# napajeniMOB.net
KiCad netlist of a schematic drawn in EAGLE
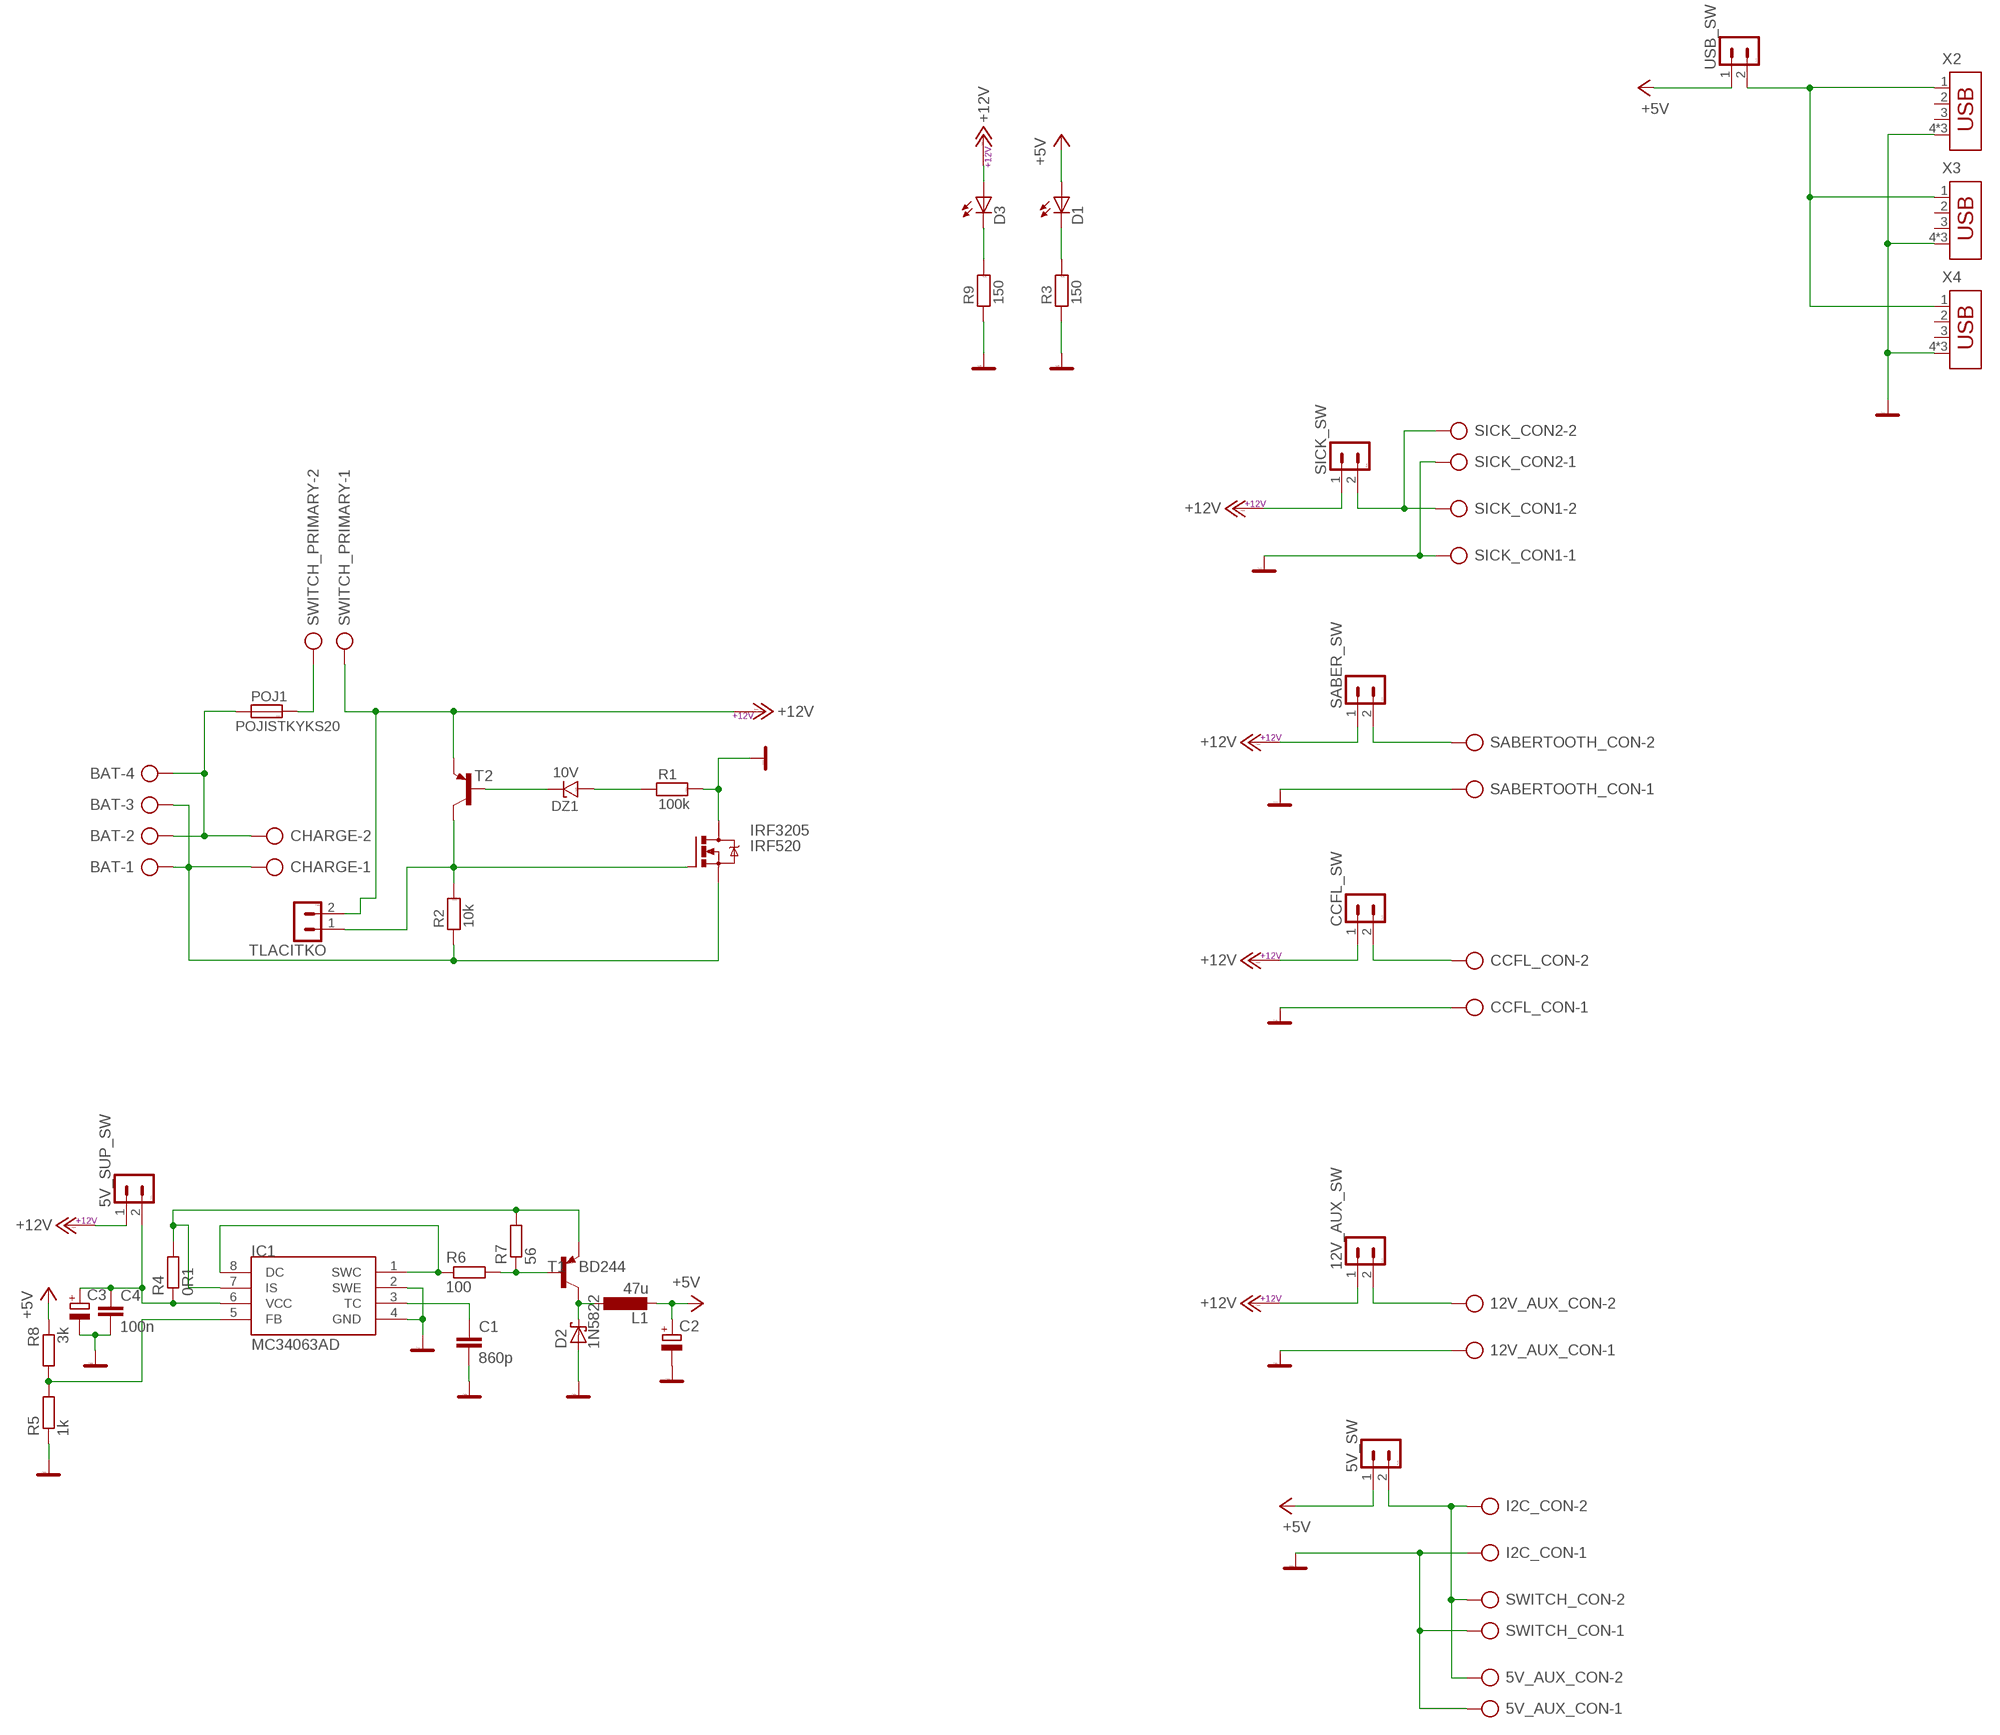
[diagram p0: schematic, sheet 1]

(export (version "E")
  (design (tool "Eeschema 10.0.6"))
  (components
    (comp (ref "5V_AUX_CON")
      (value "AK500/2")
      (footprint "eagle-import:AK500_2")
      (libsource (lib "eagle-import") (part "AK500/2"))
    )
    (comp (ref "5V_SUP_SW")
      (value "PSH02-02P")
      (footprint "eagle-import:PSH02-02P")
      (libsource (lib "eagle-import") (part "PSH02-02P"))
    )
    (comp (ref "5V_SW")
      (value "PSH02-02P")
      (footprint "eagle-import:PSH02-02P")
      (libsource (lib "eagle-import") (part "PSH02-02P"))
    )
    (comp (ref "12V_AUX_CON")
      (value "AK500/2")
      (footprint "eagle-import:AK500_2")
      (libsource (lib "eagle-import") (part "AK500/2"))
    )
    (comp (ref "12V_AUX_SW")
      (value "PSH02-02P")
      (footprint "eagle-import:PSH02-02P")
      (libsource (lib "eagle-import") (part "PSH02-02P"))
    )
    (comp (ref "BAT")
      (value "AK500/4")
      (footprint "eagle-import:AK500_4")
      (libsource (lib "eagle-import") (part "AK500/4"))
    )
    (comp (ref "C1")
      (value "860p")
      (footprint "eagle-import:C0805")
      (libsource (lib "eagle-import") (part "C-EUC0805"))
    )
    (comp (ref "C2")
      (value "CPOL-EUE5-8.5")
      (footprint "eagle-import:E5-8,5")
      (libsource (lib "eagle-import") (part "CPOL-EUE5-8.5"))
    )
    (comp (ref "C3")
      (value "CPOL-EUE5-8.5")
      (footprint "eagle-import:E5-8,5")
      (libsource (lib "eagle-import") (part "CPOL-EUE5-8.5"))
    )
    (comp (ref "C4")
      (value "100n")
      (footprint "eagle-import:C0805")
      (libsource (lib "eagle-import") (part "C-EUC0805"))
    )
    (comp (ref "CCFL_CON")
      (value "AK500/2")
      (footprint "eagle-import:AK500_2")
      (libsource (lib "eagle-import") (part "AK500/2"))
    )
    (comp (ref "CCFL_SW")
      (value "PSH02-02P")
      (footprint "eagle-import:PSH02-02P")
      (libsource (lib "eagle-import") (part "PSH02-02P"))
    )
    (comp (ref "CHARGE")
      (value "AK500/2")
      (footprint "eagle-import:AK500_2")
      (libsource (lib "eagle-import") (part "AK500/2"))
    )
    (comp (ref "D1")
      (value "LED3MM")
      (footprint "eagle-import:LED3MM")
      (libsource (lib "eagle-import") (part "LED3MM"))
    )
    (comp (ref "D2")
      (value "1N5822")
      (footprint "eagle-import:DO41-7.6")
      (libsource (lib "eagle-import") (part "1N5817-B"))
    )
    (comp (ref "D3")
      (value "LED3MM")
      (footprint "eagle-import:LED3MM")
      (libsource (lib "eagle-import") (part "LED3MM"))
    )
    (comp (ref "DZ1")
      (value "10V")
      (footprint "eagle-import:SOD-80")
      (libsource (lib "eagle-import") (part "D-ZENEROVA_0,5W_BZV55C_SMD"))
    )
    (comp (ref "I2C_CON")
      (value "AK500/2")
      (footprint "eagle-import:AK500_2")
      (libsource (lib "eagle-import") (part "AK500/2"))
    )
    (comp (ref "IC1")
      (value "MC34063AD")
      (footprint "eagle-import:SOIC8")
      (libsource (lib "eagle-import") (part "MC34063AD"))
    )
    (comp (ref "IRF3205")
      (value "IRF520")
      (footprint "eagle-import:TO220BV")
      (libsource (lib "eagle-import") (part "IRF520"))
    )
    (comp (ref "L1")
      (value "47u")
      (footprint "eagle-import:TJ3-U1")
      (libsource (lib "eagle-import") (part "L-EUTJ3-U1"))
    )
    (comp (ref "POJ1")
      (value "POJISTKYKS20")
      (footprint "eagle-import:POJ_KS20")
      (libsource (lib "eagle-import") (part "POJISTKYKS20"))
    )
    (comp (ref "R1")
      (value "100k")
      (footprint "eagle-import:0805")
      (libsource (lib "eagle-import") (part "R_SMD_0805"))
    )
    (comp (ref "R2")
      (value "10k")
      (footprint "eagle-import:0805")
      (libsource (lib "eagle-import") (part "R_SMD_0805"))
    )
    (comp (ref "R3")
      (value "150")
      (footprint "eagle-import:0805")
      (libsource (lib "eagle-import") (part "R_SMD_0805"))
    )
    (comp (ref "R4")
      (value "0R1")
      (footprint "eagle-import:M0805")
      (libsource (lib "eagle-import") (part "R-EU_M0805"))
    )
    (comp (ref "R5")
      (value "1k")
      (footprint "eagle-import:M0805")
      (libsource (lib "eagle-import") (part "R-EU_M0805"))
    )
    (comp (ref "R6")
      (value "100")
      (footprint "eagle-import:M0805")
      (libsource (lib "eagle-import") (part "R-EU_M0805"))
    )
    (comp (ref "R7")
      (value "56")
      (footprint "eagle-import:M0805")
      (libsource (lib "eagle-import") (part "R-EU_M0805"))
    )
    (comp (ref "R8")
      (value "3k")
      (footprint "eagle-import:M0805")
      (libsource (lib "eagle-import") (part "R-EU_M0805"))
    )
    (comp (ref "R9")
      (value "150")
      (footprint "eagle-import:0805")
      (libsource (lib "eagle-import") (part "R_SMD_0805"))
    )
    (comp (ref "SABERTOOTH_CON")
      (value "AK500/2")
      (footprint "eagle-import:AK500_2")
      (libsource (lib "eagle-import") (part "AK500/2"))
    )
    (comp (ref "SABER_SW")
      (value "PSH02-02P")
      (footprint "eagle-import:PSH02-02P")
      (libsource (lib "eagle-import") (part "PSH02-02P"))
    )
    (comp (ref "SICK_CON1")
      (value "AK500/2")
      (footprint "eagle-import:AK500_2")
      (libsource (lib "eagle-import") (part "AK500/2"))
    )
    (comp (ref "SICK_CON2")
      (value "AK500/2")
      (footprint "eagle-import:AK500_2")
      (libsource (lib "eagle-import") (part "AK500/2"))
    )
    (comp (ref "SICK_SW")
      (value "PSH02-02P")
      (footprint "eagle-import:PSH02-02P")
      (libsource (lib "eagle-import") (part "PSH02-02P"))
    )
    (comp (ref "SWITCH_CON")
      (value "AK500/2")
      (footprint "eagle-import:AK500_2")
      (libsource (lib "eagle-import") (part "AK500/2"))
    )
    (comp (ref "SWITCH_PRIMARY")
      (value "AK500/2")
      (footprint "eagle-import:AK500_2")
      (libsource (lib "eagle-import") (part "AK500/2"))
    )
    (comp (ref "T1")
      (value "BD244")
      (footprint "eagle-import:TO220")
      (libsource (lib "eagle-import") (part "BD244"))
    )
    (comp (ref "T2")
      (value "BC807-16-PNP-SOT23-BEC")
      (footprint "eagle-import:SOT23-BEC")
      (libsource (lib "eagle-import") (part "-PNP-SOT23-BECBC807-16"))
    )
    (comp (ref "TLACITKO")
      (value "PSH02-02P")
      (footprint "eagle-import:PSH02-02P")
      (libsource (lib "eagle-import") (part "PSH02-02P"))
    )
    (comp (ref "USB_SW")
      (value "PSH02-02P")
      (footprint "eagle-import:PSH02-02P")
      (libsource (lib "eagle-import") (part "PSH02-02P"))
    )
    (comp (ref "X2")
      (value "USB-787616GROUNDED")
      (footprint "eagle-import:USBGROUNDED")
      (libsource (lib "eagle-import") (part "USB-787616GROUNDED"))
    )
    (comp (ref "X3")
      (value "USB-787616GROUNDED")
      (footprint "eagle-import:USBGROUNDED")
      (libsource (lib "eagle-import") (part "USB-787616GROUNDED"))
    )
    (comp (ref "X4")
      (value "USB-787616GROUNDED")
      (footprint "eagle-import:USBGROUNDED")
      (libsource (lib "eagle-import") (part "USB-787616GROUNDED"))
    )
  )
  (nets
    (net (code "1") (name "+5V") (class "Default")
      (node (ref "5V_SW") (pin "1") (pinfunction "1_1") (pintype "passive"))
      (node (ref "C2") (pin "+") (pinfunction "+_+") (pintype "passive"))
      (node (ref "D1") (pin "A") (pinfunction "A_A") (pintype "passive"))
      (node (ref "L1") (pin "2") (pinfunction "2_2") (pintype "passive"))
      (node (ref "R8") (pin "1") (pinfunction "1_1") (pintype "passive"))
      (node (ref "USB_SW") (pin "1") (pinfunction "1_1") (pintype "passive"))
    )
    (net (code "2") (name "+12V") (class "Default")
      (node (ref "12V_AUX_SW") (pin "1") (pinfunction "1_1") (pintype "passive"))
      (node (ref "5V_SUP_SW") (pin "1") (pinfunction "1_1") (pintype "passive"))
      (node (ref "CCFL_SW") (pin "1") (pinfunction "1_1") (pintype "passive"))
      (node (ref "D3") (pin "A") (pinfunction "A_A") (pintype "passive"))
      (node (ref "SABER_SW") (pin "1") (pinfunction "1_1") (pintype "passive"))
      (node (ref "SICK_SW") (pin "1") (pinfunction "1_1") (pintype "passive"))
      (node (ref "SWITCH_PRIMARY") (pin "1") (pinfunction "KL_1") (pintype "passive"))
      (node (ref "T2") (pin "E") (pinfunction "E_E") (pintype "passive"))
      (node (ref "TLACITKO") (pin "2") (pinfunction "2_2") (pintype "passive"))
    )
    (net (code "3") (name "GND") (class "Default")
      (node (ref "12V_AUX_CON") (pin "1") (pinfunction "KL_1") (pintype "passive"))
      (node (ref "5V_AUX_CON") (pin "1") (pinfunction "KL_1") (pintype "passive"))
      (node (ref "C1") (pin "2") (pinfunction "2_2") (pintype "passive"))
      (node (ref "C2") (pin "-") (pinfunction "-_-") (pintype "passive"))
      (node (ref "C3") (pin "-") (pinfunction "-_-") (pintype "passive"))
      (node (ref "C4") (pin "2") (pinfunction "2_2") (pintype "passive"))
      (node (ref "CCFL_CON") (pin "1") (pinfunction "KL_1") (pintype "passive"))
      (node (ref "D2") (pin "A") (pinfunction "A_A") (pintype "passive"))
      (node (ref "I2C_CON") (pin "1") (pinfunction "KL_1") (pintype "passive"))
      (node (ref "IC1") (pin "2") (pinfunction "SWE_2") (pintype "passive"))
      (node (ref "IC1") (pin "4") (pinfunction "GND_4") (pintype "passive"))
      (node (ref "IRF3205") (pin "D") (pinfunction "D_D") (pintype "passive"))
      (node (ref "R1") (pin "2") (pinfunction "2_2") (pintype "passive"))
      (node (ref "R3") (pin "1") (pinfunction "1_1") (pintype "passive"))
      (node (ref "R5") (pin "1") (pinfunction "1_1") (pintype "passive"))
      (node (ref "R9") (pin "1") (pinfunction "1_1") (pintype "passive"))
      (node (ref "SABERTOOTH_CON") (pin "1") (pinfunction "KL_1") (pintype "passive"))
      (node (ref "SICK_CON1") (pin "1") (pinfunction "KL_1") (pintype "passive"))
      (node (ref "SICK_CON2") (pin "1") (pinfunction "KL_1") (pintype "passive"))
      (node (ref "SWITCH_CON") (pin "1") (pinfunction "KL_1") (pintype "passive"))
      (node (ref "X2") (pin "4") (pinfunction "4_4") (pintype "passive"))
      (node (ref "X2") (pin "S1") (pinfunction "4_S1") (pintype "passive"))
      (node (ref "X2") (pin "S2") (pinfunction "4_S2") (pintype "passive"))
      (node (ref "X3") (pin "4") (pinfunction "4_4") (pintype "passive"))
      (node (ref "X3") (pin "S1") (pinfunction "4_S1") (pintype "passive"))
      (node (ref "X3") (pin "S2") (pinfunction "4_S2") (pintype "passive"))
      (node (ref "X4") (pin "4") (pinfunction "4_4") (pintype "passive"))
      (node (ref "X4") (pin "S1") (pinfunction "4_S1") (pintype "passive"))
      (node (ref "X4") (pin "S2") (pinfunction "4_S2") (pintype "passive"))
    )
    (net (code "4") (name "Net-(5V_AUX_CONB-KL)") (class "Default")
      (node (ref "5V_AUX_CON") (pin "2") (pinfunction "KL_2") (pintype "passive"))
      (node (ref "5V_SW") (pin "2") (pinfunction "2_2") (pintype "passive"))
      (node (ref "I2C_CON") (pin "2") (pinfunction "KL_2") (pintype "passive"))
      (node (ref "SWITCH_CON") (pin "2") (pinfunction "KL_2") (pintype "passive"))
    )
    (net (code "5") (name "Net-(12V_AUX_CONB-KL)") (class "Default")
      (node (ref "12V_AUX_CON") (pin "2") (pinfunction "KL_2") (pintype "passive"))
      (node (ref "12V_AUX_SW") (pin "2") (pinfunction "2_2") (pintype "passive"))
    )
    (net (code "6") (name "Net-(BATA-KL)") (class "Default")
      (node (ref "BAT") (pin "1") (pinfunction "KL_1") (pintype "passive"))
      (node (ref "BAT") (pin "3") (pinfunction "KL_3") (pintype "passive"))
      (node (ref "CHARGE") (pin "1") (pinfunction "KL_1") (pintype "passive"))
      (node (ref "IRF3205") (pin "S") (pinfunction "S_S") (pintype "passive"))
      (node (ref "R2") (pin "1") (pinfunction "1_1") (pintype "passive"))
    )
    (net (code "7") (name "Net-(BATB-KL)") (class "Default")
      (node (ref "BAT") (pin "2") (pinfunction "KL_2") (pintype "passive"))
      (node (ref "BAT") (pin "4") (pinfunction "KL_4") (pintype "passive"))
      (node (ref "CHARGE") (pin "2") (pinfunction "KL_2") (pintype "passive"))
      (node (ref "POJ1") (pin "1") (pinfunction "1_1") (pintype "passive"))
    )
    (net (code "8") (name "Net-(CCFL_CONB-KL)") (class "Default")
      (node (ref "CCFL_CON") (pin "2") (pinfunction "KL_2") (pintype "passive"))
      (node (ref "CCFL_SW") (pin "2") (pinfunction "2_2") (pintype "passive"))
    )
    (net (code "9") (name "Net-(D1-C)") (class "Default")
      (node (ref "D1") (pin "K") (pinfunction "C_K") (pintype "passive"))
      (node (ref "R3") (pin "2") (pinfunction "2_2") (pintype "passive"))
    )
    (net (code "10") (name "Net-(D3-C)") (class "Default")
      (node (ref "D3") (pin "K") (pinfunction "C_K") (pintype "passive"))
      (node (ref "R9") (pin "2") (pinfunction "2_2") (pintype "passive"))
    )
    (net (code "11") (name "Net-(DZ1-PadA)") (class "Default")
      (node (ref "DZ1") (pin "A") (pinfunction "A_A") (pintype "passive"))
      (node (ref "R1") (pin "1") (pinfunction "1_1") (pintype "passive"))
    )
    (net (code "12") (name "Net-(DZ1-PadK)") (class "Default")
      (node (ref "DZ1") (pin "K") (pinfunction "K_K") (pintype "passive"))
      (node (ref "T2") (pin "B") (pinfunction "B_B") (pintype "passive"))
    )
    (net (code "13") (name "Net-(IC1-DC)") (class "Default")
      (node (ref "IC1") (pin "1") (pinfunction "SWC_1") (pintype "passive"))
      (node (ref "IC1") (pin "8") (pinfunction "DC_8") (pintype "passive"))
      (node (ref "R6") (pin "1") (pinfunction "1_1") (pintype "passive"))
    )
    (net (code "14") (name "Net-(IC1-FB)") (class "Default")
      (node (ref "IC1") (pin "5") (pinfunction "FB_5") (pintype "passive"))
      (node (ref "R5") (pin "2") (pinfunction "2_2") (pintype "passive"))
      (node (ref "R8") (pin "2") (pinfunction "2_2") (pintype "passive"))
    )
    (net (code "15") (name "Net-(IC1-IS)") (class "Default")
      (node (ref "IC1") (pin "7") (pinfunction "IS_7") (pintype "passive"))
      (node (ref "R4") (pin "2") (pinfunction "2_2") (pintype "passive"))
      (node (ref "R7") (pin "2") (pinfunction "2_2") (pintype "passive"))
      (node (ref "T1") (pin "3") (pinfunction "E_3") (pintype "passive"))
    )
    (net (code "16") (name "Net-(IC1-TC)") (class "Default")
      (node (ref "C1") (pin "1") (pinfunction "1_1") (pintype "passive"))
      (node (ref "IC1") (pin "3") (pinfunction "TC_3") (pintype "passive"))
    )
    (net (code "17") (name "Net-(IC1-VCC)") (class "Default")
      (node (ref "5V_SUP_SW") (pin "2") (pinfunction "2_2") (pintype "passive"))
      (node (ref "C3") (pin "+") (pinfunction "+_+") (pintype "passive"))
      (node (ref "C4") (pin "1") (pinfunction "1_1") (pintype "passive"))
      (node (ref "IC1") (pin "6") (pinfunction "VCC_6") (pintype "passive"))
      (node (ref "R4") (pin "1") (pinfunction "1_1") (pintype "passive"))
    )
    (net (code "18") (name "Net-(IRF3205-PadG)") (class "Default")
      (node (ref "IRF3205") (pin "G") (pinfunction "G_G") (pintype "passive"))
      (node (ref "R2") (pin "2") (pinfunction "2_2") (pintype "passive"))
      (node (ref "T2") (pin "C") (pinfunction "C_C") (pintype "passive"))
      (node (ref "TLACITKO") (pin "1") (pinfunction "1_1") (pintype "passive"))
    )
    (net (code "19") (name "Net-(SABERTOOTH_CONB-KL)") (class "Default")
      (node (ref "SABERTOOTH_CON") (pin "2") (pinfunction "KL_2") (pintype "passive"))
      (node (ref "SABER_SW") (pin "2") (pinfunction "2_2") (pintype "passive"))
    )
    (net (code "20") (name "Net-(SICK_CON1B-KL)") (class "Default")
      (node (ref "SICK_CON1") (pin "2") (pinfunction "KL_2") (pintype "passive"))
      (node (ref "SICK_CON2") (pin "2") (pinfunction "KL_2") (pintype "passive"))
      (node (ref "SICK_SW") (pin "2") (pinfunction "2_2") (pintype "passive"))
    )
    (net (code "21") (name "Net-(SWITCH_PRIMARYB-KL)") (class "Default")
      (node (ref "POJ1") (pin "2") (pinfunction "2_2") (pintype "passive"))
      (node (ref "SWITCH_PRIMARY") (pin "2") (pinfunction "KL_2") (pintype "passive"))
    )
    (net (code "22") (name "Net-(T1-B)") (class "Default")
      (node (ref "R6") (pin "2") (pinfunction "2_2") (pintype "passive"))
      (node (ref "R7") (pin "1") (pinfunction "1_1") (pintype "passive"))
      (node (ref "T1") (pin "1") (pinfunction "B_1") (pintype "passive"))
    )
    (net (code "23") (name "Net-(T1-C)") (class "Default")
      (node (ref "D2") (pin "C") (pinfunction "C_C") (pintype "passive"))
      (node (ref "L1") (pin "1") (pinfunction "1_1") (pintype "passive"))
      (node (ref "T1") (pin "2") (pinfunction "C_2") (pintype "passive"))
    )
    (net (code "24") (name "Net-(USB_SW-Pad2)") (class "Default")
      (node (ref "USB_SW") (pin "2") (pinfunction "2_2") (pintype "passive"))
      (node (ref "X2") (pin "1") (pinfunction "1_1") (pintype "passive"))
      (node (ref "X3") (pin "1") (pinfunction "1_1") (pintype "passive"))
      (node (ref "X4") (pin "1") (pinfunction "1_1") (pintype "passive"))
    )
    (net (code "25") (name "unconnected-(X2-Pad2)") (class "Default")
      (node (ref "X2") (pin "2") (pinfunction "2_2") (pintype "passive"))
    )
    (net (code "26") (name "unconnected-(X2-Pad3)") (class "Default")
      (node (ref "X2") (pin "3") (pinfunction "3_3") (pintype "passive"))
    )
    (net (code "27") (name "unconnected-(X3-Pad2)") (class "Default")
      (node (ref "X3") (pin "2") (pinfunction "2_2") (pintype "passive"))
    )
    (net (code "28") (name "unconnected-(X3-Pad3)") (class "Default")
      (node (ref "X3") (pin "3") (pinfunction "3_3") (pintype "passive"))
    )
    (net (code "29") (name "unconnected-(X4-Pad2)") (class "Default")
      (node (ref "X4") (pin "2") (pinfunction "2_2") (pintype "passive"))
    )
    (net (code "30") (name "unconnected-(X4-Pad3)") (class "Default")
      (node (ref "X4") (pin "3") (pinfunction "3_3") (pintype "passive"))
    )
  )
)
